# MCU.net
KiCad netlist of a schematic drawn in Altium Designer
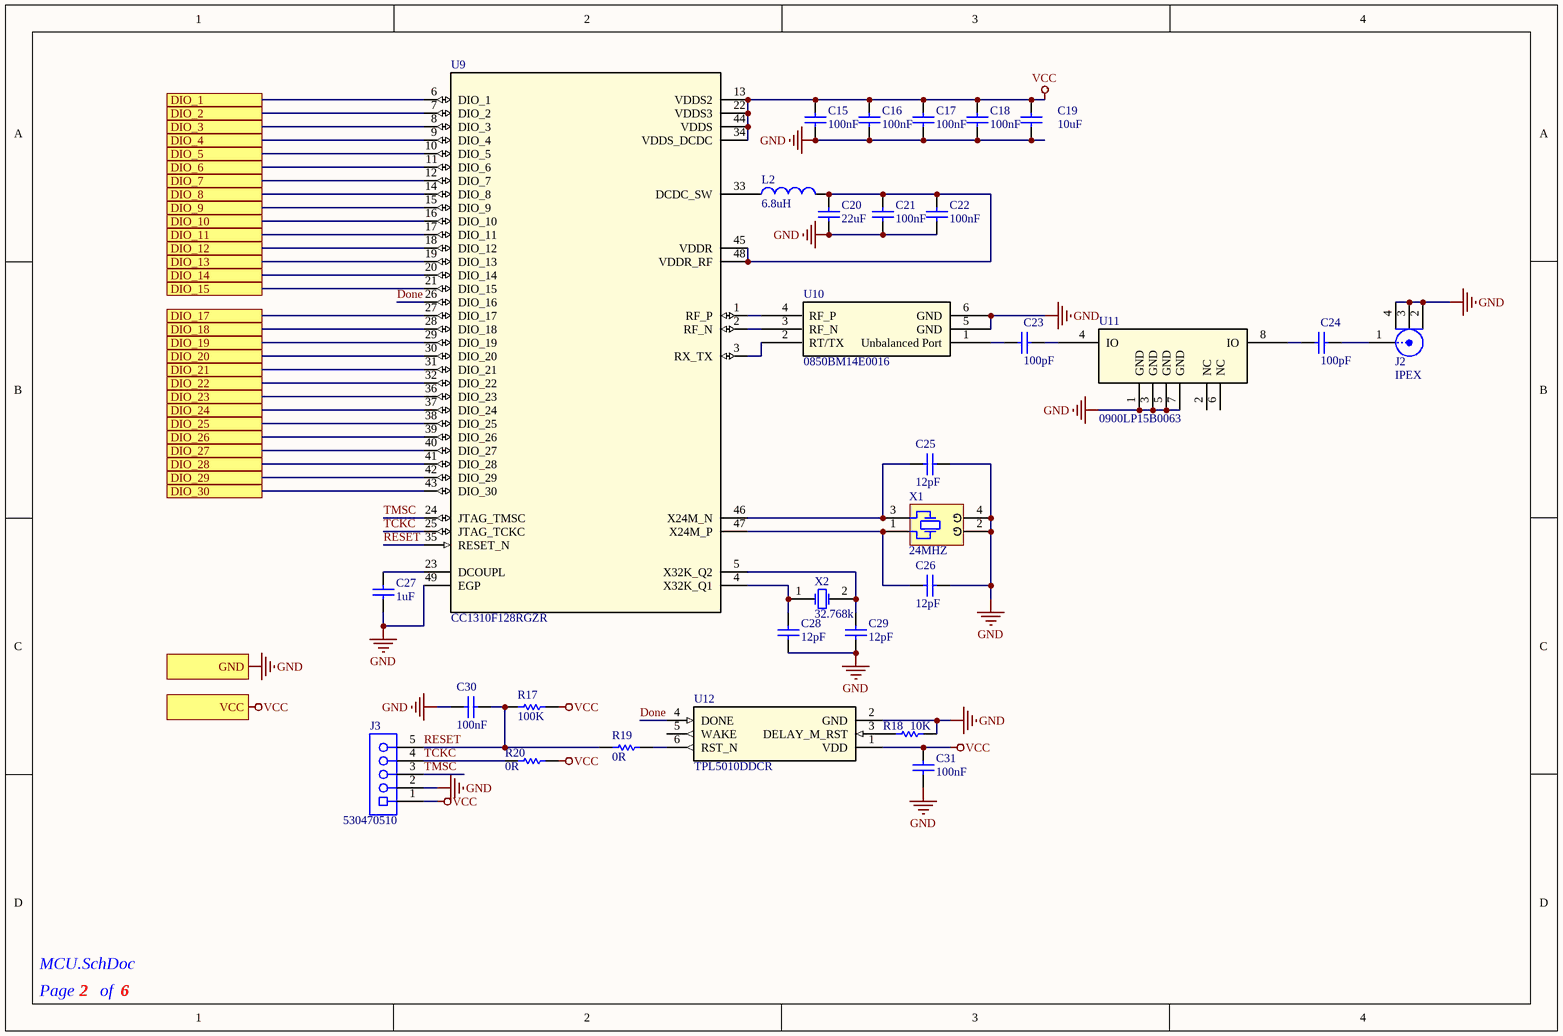
[diagram p0: MCU.SchDoc]

(export (version "E")
  (design (tool "Eeschema 10.0.6"))
  (components
    (comp (ref "C15")
      (value "100nF")
      (footprint "R0603_C")
      (description "精度 ±10% \r\n容值 100nF \r\n额定电压 50V \r\n温漂系数（介质材料) X7R")
      (libsource (lib "00Lib") (part "100nF/0603/50V"))
    )
    (comp (ref "C16")
      (value "100nF")
      (footprint "R0603_C")
      (description "精度 ±10% \r\n容值 100nF \r\n额定电压 50V \r\n温漂系数（介质材料) X7R")
      (libsource (lib "00Lib") (part "100nF/0603/50V"))
    )
    (comp (ref "C17")
      (value "100nF")
      (footprint "R0603_C")
      (description "精度 ±10% \r\n容值 100nF \r\n额定电压 50V \r\n温漂系数（介质材料) X7R")
      (libsource (lib "00Lib") (part "100nF/0603/50V"))
    )
    (comp (ref "C18")
      (value "100nF")
      (footprint "R0603_C")
      (description "精度 ±10% \r\n容值 100nF \r\n额定电压 50V \r\n温漂系数（介质材料) X7R")
      (libsource (lib "00Lib") (part "100nF/0603/50V"))
    )
    (comp (ref "C19")
      (value "10uF")
      (footprint "R0805_C")
      (description "精度 ±10% \r\n容值 10uF \r\n额定电压 16V \r\n温漂系数（介质材料) X7R")
      (libsource (lib "00Lib") (part "10uF/0805/16V"))
    )
    (comp (ref "C20")
      (value "22uF")
      (footprint "R0805_C")
      (description "精度 ±20% \r\n容值 22uF \r\n额定电压 16V \r\n温漂系数（介质材料) X5R")
      (libsource (lib "00Lib") (part "22uF/0805/16V"))
    )
    (comp (ref "C21")
      (value "100nF")
      (footprint "R0603_C")
      (description "精度 ±10% \r\n容值 100nF \r\n额定电压 50V \r\n温漂系数（介质材料) X7R")
      (libsource (lib "00Lib") (part "100nF/0603/50V"))
    )
    (comp (ref "C22")
      (value "100nF")
      (footprint "R0603_C")
      (description "精度 ±10% \r\n容值 100nF \r\n额定电压 50V \r\n温漂系数（介质材料) X7R")
      (libsource (lib "00Lib") (part "100nF/0603/50V"))
    )
    (comp (ref "C23")
      (value "100pF")
      (footprint "R0402_C")
      (description "精度 ±5% \r\n容值 100pF \r\n额定电压 50V \r\n温漂系数（介质材料) C0G")
      (libsource (lib "00Lib") (part "100pF/0402/50V"))
    )
    (comp (ref "C24")
      (value "100pF")
      (footprint "R0402_C")
      (description "精度 ±5% \r\n容值 100pF \r\n额定电压 50V \r\n温漂系数（介质材料) C0G")
      (libsource (lib "00Lib") (part "100pF/0402/50V"))
    )
    (comp (ref "C25")
      (value "12pF")
      (footprint "R0402_C")
      (description "精度 ±1% \r\n容值 12pF \r\n额定电压 50V \r\n温漂系数（介质材料) C0G")
      (libsource (lib "00Lib") (part "12pF/0402/50V"))
    )
    (comp (ref "C26")
      (value "12pF")
      (footprint "R0402_C")
      (description "精度 ±1% \r\n容值 12pF \r\n额定电压 50V \r\n温漂系数（介质材料) C0G")
      (libsource (lib "00Lib") (part "12pF/0402/50V"))
    )
    (comp (ref "C27")
      (value "1uF")
      (footprint "R0603_C")
      (description "精度 ±10% \r\n容值 1uF \r\n额定电压 50V \r\n温漂系数（介质材料) X7R")
      (libsource (lib "00Lib") (part "1uF/0603/50V"))
    )
    (comp (ref "C28")
      (value "12pF")
      (footprint "R0402_C")
      (description "精度 ±1% \r\n容值 12pF \r\n额定电压 50V \r\n温漂系数（介质材料) C0G")
      (libsource (lib "00Lib") (part "12pF/0402/50V"))
    )
    (comp (ref "C29")
      (value "12pF")
      (footprint "R0402_C")
      (description "精度 ±1% \r\n容值 12pF \r\n额定电压 50V \r\n温漂系数（介质材料) C0G")
      (libsource (lib "00Lib") (part "12pF/0402/50V"))
    )
    (comp (ref "C30")
      (value "100nF")
      (footprint "R0603_C")
      (description "精度 ±10% \r\n容值 100nF \r\n额定电压 50V \r\n温漂系数（介质材料) X7R")
      (libsource (lib "00Lib") (part "100nF/0603/50V"))
    )
    (comp (ref "C31")
      (value "100nF")
      (footprint "R0603_C")
      (description "精度 ±10% \r\n容值 100nF \r\n额定电压 50V \r\n温漂系数（介质材料) X7R")
      (libsource (lib "00Lib") (part "100nF/0603/50V"))
    )
    (comp (ref "J2")
      (value "IPEX")
      (footprint "molex-73412")
      (description "RF同轴连接器（天线座）")
      (libsource (lib "00Lib") (part "73412-0110"))
    )
    (comp (ref "J3")
      (value "530470510")
      (footprint "1.25mm_p5")
      (description "MX1.25 直插 镀锡 5P 针座")
      (libsource (lib "00Lib") (part "Molex-530470510"))
    )
    (comp (ref "L2")
      (value "6.8uH")
      (footprint "R0805_L")
      (description "精度 ±10% \r\n电感值 6.8uH \r\n直流电阻（内阻） 250mΩ \r\n额定电流 250mA")
      (libsource (lib "00Lib") (part "6.8uH/0805"))
    )
    (comp (ref "R17")
      (value "100K")
      (footprint "R0603_R")
      (description "精度 ±1% \r\n阻值 100kΩ \r\n温度系数 ±100ppm/℃ \r\n功率 0.1W")
      (libsource (lib "00Lib") (part "100K/0603"))
    )
    (comp (ref "R18")
      (value "10K")
      (footprint "R0603_R")
      (description "精度 ±1% \r\n温度系数 ±100ppm/℃ \r\n阻值 10kΩ \r\n功率 0.1W")
      (libsource (lib "00Lib") (part "10K/0603"))
    )
    (comp (ref "R19")
      (value "0R")
      (footprint "R0603_R")
      (description "精度 ±1% \r\n阻值 0Ω \r\n功率 0.1W")
      (libsource (lib "00Lib") (part "0R/0603"))
    )
    (comp (ref "R20")
      (value "0R")
      (footprint "R0603_R")
      (description "精度 ±1% \r\n阻值 0Ω \r\n功率 0.1W")
      (libsource (lib "00Lib") (part "0R/0603"))
    )
    (comp (ref "U9")
      (value "CC1310F128RGZR")
      (footprint "RGZ0048A")
      (description "RF-MCU")
      (libsource (lib "00Lib") (part "CC1310F128RGZR"))
    )
    (comp (ref "U10")
      (value "0850BM14E0016")
      (footprint "6P0603")
      (description "770 - 860 860 - 928MHz\r\n-40°C to +85°C\r\nPmax 2W")
      (libsource (lib "00Lib") (part "0850BM14E0016"))
    )
    (comp (ref "U11")
      (value "0900LP15B0063")
      (footprint "8P0805")
      (libsource (lib "00Lib") (part "0900LP15B0063"))
    )
    (comp (ref "U12")
      (value "TPL5010DDCR")
      (footprint "DBV0006A_N")
      (description "看门狗")
      (libsource (lib "00Lib") (part "TPL5010DDCR"))
    )
    (comp (ref "X1")
      (value "24MHZ")
      (footprint "SMD-3225")
      (description "等效串联电阻（ESR） 40Ω \r\n无源贴片晶振 \r\n主频 24MHz \r\n频率公差 ±10ppm \r\n负载电容值 9pF \r\n工作温度 -40℃~85℃")
      (libsource (lib "00Lib") (part "X1E000021012700"))
    )
    (comp (ref "X2")
      (value "32.768k")
      (footprint "FC-135")
      (libsource (lib "00Lib") (part "FC-135 32.768KHz ±20ppm 12.5pF"))
    )
  )
  (nets
    (net (code "1") (name "/DIO_1") (class "Default")
      (node (ref "U9") (pin "6") (pinfunction "DIO_1_6") (pintype "bidirectional"))
    )
    (net (code "2") (name "/DIO_2") (class "Default")
      (node (ref "U9") (pin "7") (pinfunction "DIO_2_7") (pintype "bidirectional"))
    )
    (net (code "3") (name "/DIO_3") (class "Default")
      (node (ref "U9") (pin "8") (pinfunction "DIO_3_8") (pintype "bidirectional"))
    )
    (net (code "4") (name "/DIO_4") (class "Default")
      (node (ref "U9") (pin "9") (pinfunction "DIO_4_9") (pintype "bidirectional"))
    )
    (net (code "5") (name "/DIO_5") (class "Default")
      (node (ref "U9") (pin "10") (pinfunction "DIO_5_10") (pintype "bidirectional"))
    )
    (net (code "6") (name "/DIO_6") (class "Default")
      (node (ref "U9") (pin "11") (pinfunction "DIO_6_11") (pintype "bidirectional"))
    )
    (net (code "7") (name "/DIO_7") (class "Default")
      (node (ref "U9") (pin "12") (pinfunction "DIO_7_12") (pintype "bidirectional"))
    )
    (net (code "8") (name "/DIO_8") (class "Default")
      (node (ref "U9") (pin "14") (pinfunction "DIO_8_14") (pintype "bidirectional"))
    )
    (net (code "9") (name "/DIO_9") (class "Default")
      (node (ref "U9") (pin "15") (pinfunction "DIO_9_15") (pintype "bidirectional"))
    )
    (net (code "10") (name "/DIO_10") (class "Default")
      (node (ref "U9") (pin "16") (pinfunction "DIO_10_16") (pintype "bidirectional"))
    )
    (net (code "11") (name "/DIO_11") (class "Default")
      (node (ref "U9") (pin "17") (pinfunction "DIO_11_17") (pintype "bidirectional"))
    )
    (net (code "12") (name "/DIO_12") (class "Default")
      (node (ref "U9") (pin "18") (pinfunction "DIO_12_18") (pintype "bidirectional"))
    )
    (net (code "13") (name "/DIO_13") (class "Default")
      (node (ref "U9") (pin "19") (pinfunction "DIO_13_19") (pintype "bidirectional"))
    )
    (net (code "14") (name "/DIO_14") (class "Default")
      (node (ref "U9") (pin "20") (pinfunction "DIO_14_20") (pintype "bidirectional"))
    )
    (net (code "15") (name "/DIO_15") (class "Default")
      (node (ref "U9") (pin "21") (pinfunction "DIO_15_21") (pintype "bidirectional"))
    )
    (net (code "16") (name "/DIO_17") (class "Default")
      (node (ref "U9") (pin "27") (pinfunction "DIO_17_27") (pintype "bidirectional"))
    )
    (net (code "17") (name "/DIO_18") (class "Default")
      (node (ref "U9") (pin "28") (pinfunction "DIO_18_28") (pintype "bidirectional"))
    )
    (net (code "18") (name "/DIO_19") (class "Default")
      (node (ref "U9") (pin "29") (pinfunction "DIO_19_29") (pintype "bidirectional"))
    )
    (net (code "19") (name "/DIO_20") (class "Default")
      (node (ref "U9") (pin "30") (pinfunction "DIO_20_30") (pintype "bidirectional"))
    )
    (net (code "20") (name "/DIO_21") (class "Default")
      (node (ref "U9") (pin "31") (pinfunction "DIO_21_31") (pintype "bidirectional"))
    )
    (net (code "21") (name "/DIO_22") (class "Default")
      (node (ref "U9") (pin "32") (pinfunction "DIO_22_32") (pintype "bidirectional"))
    )
    (net (code "22") (name "/DIO_23") (class "Default")
      (node (ref "U9") (pin "36") (pinfunction "DIO_23_36") (pintype "bidirectional"))
    )
    (net (code "23") (name "/DIO_24") (class "Default")
      (node (ref "U9") (pin "37") (pinfunction "DIO_24_37") (pintype "bidirectional"))
    )
    (net (code "24") (name "/DIO_25") (class "Default")
      (node (ref "U9") (pin "38") (pinfunction "DIO_25_38") (pintype "bidirectional"))
    )
    (net (code "25") (name "/DIO_26") (class "Default")
      (node (ref "U9") (pin "39") (pinfunction "DIO_26_39") (pintype "bidirectional"))
    )
    (net (code "26") (name "/DIO_27") (class "Default")
      (node (ref "U9") (pin "40") (pinfunction "DIO_27_40") (pintype "bidirectional"))
    )
    (net (code "27") (name "/DIO_28") (class "Default")
      (node (ref "U9") (pin "41") (pinfunction "DIO_28_41") (pintype "bidirectional"))
    )
    (net (code "28") (name "/DIO_29") (class "Default")
      (node (ref "U9") (pin "42") (pinfunction "DIO_29_42") (pintype "bidirectional"))
    )
    (net (code "29") (name "/DIO_30") (class "Default")
      (node (ref "U9") (pin "43") (pinfunction "DIO_30_43") (pintype "bidirectional"))
    )
    (net (code "30") (name "/Done") (class "Default")
      (node (ref "U12") (pin "4") (pinfunction "DONE_4") (pintype "input"))
      (node (ref "U9") (pin "26") (pinfunction "DIO_16_26") (pintype "bidirectional"))
    )
    (net (code "31") (name "/RESET") (class "Default")
      (node (ref "C30") (pin "1") (pinfunction "1_1") (pintype "passive"))
      (node (ref "J3") (pin "5") (pinfunction "5_5") (pintype "passive"))
      (node (ref "R17") (pin "1") (pinfunction "1_1") (pintype "passive"))
      (node (ref "R19") (pin "2") (pinfunction "2_2") (pintype "passive"))
      (node (ref "U9") (pin "35") (pinfunction "RESET_N_35") (pintype "input"))
    )
    (net (code "32") (name "/TCKC") (class "Default")
      (node (ref "J3") (pin "4") (pinfunction "4_4") (pintype "passive"))
      (node (ref "R20") (pin "2") (pinfunction "2_2") (pintype "passive"))
      (node (ref "U9") (pin "25") (pinfunction "JTAG_TCKC_25") (pintype "bidirectional"))
    )
    (net (code "33") (name "/TMSC") (class "Default")
      (node (ref "J3") (pin "3") (pinfunction "3_3") (pintype "passive"))
      (node (ref "U9") (pin "24") (pinfunction "JTAG_TMSC_24") (pintype "bidirectional"))
    )
    (net (code "34") (name "GND") (class "Default")
      (node (ref "C15") (pin "1") (pinfunction "1_1") (pintype "passive"))
      (node (ref "C16") (pin "1") (pinfunction "1_1") (pintype "passive"))
      (node (ref "C17") (pin "1") (pinfunction "1_1") (pintype "passive"))
      (node (ref "C18") (pin "1") (pinfunction "1_1") (pintype "passive"))
      (node (ref "C19") (pin "1") (pinfunction "1_1") (pintype "passive"))
      (node (ref "C20") (pin "1") (pinfunction "1_1") (pintype "passive"))
      (node (ref "C21") (pin "1") (pinfunction "1_1") (pintype "passive"))
      (node (ref "C22") (pin "1") (pinfunction "1_1") (pintype "passive"))
      (node (ref "C25") (pin "1") (pinfunction "1_1") (pintype "passive"))
      (node (ref "C26") (pin "1") (pinfunction "1_1") (pintype "passive"))
      (node (ref "C27") (pin "1") (pinfunction "1_1") (pintype "passive"))
      (node (ref "C28") (pin "1") (pinfunction "1_1") (pintype "passive"))
      (node (ref "C29") (pin "1") (pinfunction "1_1") (pintype "passive"))
      (node (ref "C30") (pin "2") (pinfunction "2_2") (pintype "passive"))
      (node (ref "C31") (pin "1") (pinfunction "1_1") (pintype "passive"))
      (node (ref "J2") (pin "2") (pinfunction "2_2") (pintype "passive"))
      (node (ref "J2") (pin "3") (pinfunction "3_3") (pintype "passive"))
      (node (ref "J2") (pin "4") (pinfunction "4_4") (pintype "passive"))
      (node (ref "J3") (pin "2") (pinfunction "2_2") (pintype "passive"))
      (node (ref "R18") (pin "1") (pinfunction "1_1") (pintype "passive"))
      (node (ref "U10") (pin "5") (pinfunction "GND_5") (pintype "passive"))
      (node (ref "U10") (pin "6") (pinfunction "GND_6") (pintype "passive"))
      (node (ref "U11") (pin "1") (pinfunction "GND_1") (pintype "passive"))
      (node (ref "U11") (pin "3") (pinfunction "GND_3") (pintype "passive"))
      (node (ref "U11") (pin "5") (pinfunction "GND_5") (pintype "passive"))
      (node (ref "U11") (pin "7") (pinfunction "GND_7") (pintype "passive"))
      (node (ref "U12") (pin "2") (pinfunction "GND_2") (pintype "power_in"))
      (node (ref "U9") (pin "49") (pinfunction "EGP_49") (pintype "power_in"))
      (node (ref "X1") (pin "2") (pinfunction "GND_2") (pintype "power_in"))
      (node (ref "X1") (pin "4") (pinfunction "GND_4") (pintype "power_in"))
    )
    (net (code "35") (name "Net-(C23-Pad2)") (class "Default")
      (node (ref "C23") (pin "2") (pinfunction "2_2") (pintype "passive"))
      (node (ref "U11") (pin "4") (pinfunction "IO_4") (pintype "passive"))
    )
    (net (code "36") (name "Net-(C24-Pad1)") (class "Default")
      (node (ref "C24") (pin "1") (pinfunction "1_1") (pintype "passive"))
      (node (ref "U11") (pin "8") (pinfunction "IO_8") (pintype "passive"))
    )
    (net (code "37") (name "Net-(C24-Pad2)") (class "Default")
      (node (ref "C24") (pin "2") (pinfunction "2_2") (pintype "passive"))
      (node (ref "J2") (pin "1") (pinfunction "1_1") (pintype "passive"))
    )
    (net (code "38") (name "Net-(U9-DCDC_SW)") (class "Default")
      (node (ref "L2") (pin "1") (pinfunction "1_1") (pintype "passive"))
      (node (ref "U9") (pin "33") (pinfunction "DCDC_SW_33") (pintype "power_in"))
    )
    (net (code "39") (name "Net-(U9-DCOUPL)") (class "Default")
      (node (ref "C27") (pin "2") (pinfunction "2_2") (pintype "passive"))
      (node (ref "U9") (pin "23") (pinfunction "DCOUPL_23") (pintype "passive"))
    )
    (net (code "40") (name "Net-(U9-VDDR)") (class "Default")
      (node (ref "C20") (pin "2") (pinfunction "2_2") (pintype "passive"))
      (node (ref "C21") (pin "2") (pinfunction "2_2") (pintype "passive"))
      (node (ref "C22") (pin "2") (pinfunction "2_2") (pintype "passive"))
      (node (ref "L2") (pin "2") (pinfunction "2_2") (pintype "passive"))
      (node (ref "U9") (pin "45") (pinfunction "VDDR_45") (pintype "power_in"))
      (node (ref "U9") (pin "48") (pinfunction "VDDR_RF_48") (pintype "power_in"))
    )
    (net (code "41") (name "Net-(U9-X24M_N)") (class "Default")
      (node (ref "C25") (pin "2") (pinfunction "2_2") (pintype "passive"))
      (node (ref "U9") (pin "46") (pinfunction "X24M_N_46") (pintype "passive"))
      (node (ref "X1") (pin "3") (pinfunction "3_3") (pintype "passive"))
    )
    (net (code "42") (name "Net-(U9-X24M_P)") (class "Default")
      (node (ref "C26") (pin "2") (pinfunction "2_2") (pintype "passive"))
      (node (ref "U9") (pin "47") (pinfunction "X24M_P_47") (pintype "passive"))
      (node (ref "X1") (pin "1") (pinfunction "1_1") (pintype "passive"))
    )
    (net (code "43") (name "Net-(U9-X32K_Q1)") (class "Default")
      (node (ref "C28") (pin "2") (pinfunction "2_2") (pintype "passive"))
      (node (ref "U9") (pin "4") (pinfunction "X32K_Q1_4") (pintype "passive"))
      (node (ref "X2") (pin "1") (pinfunction "OSC1_1") (pintype "passive"))
    )
    (net (code "44") (name "Net-(U9-X32K_Q2)") (class "Default")
      (node (ref "C29") (pin "2") (pinfunction "2_2") (pintype "passive"))
      (node (ref "U9") (pin "5") (pinfunction "X32K_Q2_5") (pintype "passive"))
      (node (ref "X2") (pin "2") (pinfunction "OSC2_2") (pintype "passive"))
    )
    (net (code "45") (name "Net-(U10-RF_N)") (class "Default")
      (node (ref "U10") (pin "3") (pinfunction "RF_N_3") (pintype "passive"))
      (node (ref "U9") (pin "2") (pinfunction "RF_N_2") (pintype "bidirectional"))
    )
    (net (code "46") (name "Net-(U10-RF_P)") (class "Default")
      (node (ref "U10") (pin "4") (pinfunction "RF_P_4") (pintype "passive"))
      (node (ref "U9") (pin "1") (pinfunction "RF_P_1") (pintype "bidirectional"))
    )
    (net (code "47") (name "Net-(U10-RT{slash}TX)") (class "Default")
      (node (ref "U10") (pin "2") (pinfunction "RT/TX_2") (pintype "passive"))
      (node (ref "U9") (pin "3") (pinfunction "RX_TX_3") (pintype "bidirectional"))
    )
    (net (code "48") (name "Net-(U10-Unbalanced_Port)") (class "Default")
      (node (ref "C23") (pin "1") (pinfunction "1_1") (pintype "passive"))
      (node (ref "U10") (pin "1") (pinfunction "Unbalanced_Port_1") (pintype "passive"))
    )
    (net (code "49") (name "Net-(U12-DELAY_M_RST)") (class "Default")
      (node (ref "R18") (pin "2") (pinfunction "2_2") (pintype "passive"))
      (node (ref "U12") (pin "3") (pinfunction "DELAY_M_RST_3") (pintype "input"))
    )
    (net (code "50") (name "Net-(U12-RST_N)") (class "Default")
      (node (ref "R19") (pin "1") (pinfunction "1_1") (pintype "passive"))
      (node (ref "U12") (pin "6") (pinfunction "RST_N_6") (pintype "output"))
    )
    (net (code "51") (name "VCC") (class "Default")
      (node (ref "C15") (pin "2") (pinfunction "2_2") (pintype "passive"))
      (node (ref "C16") (pin "2") (pinfunction "2_2") (pintype "passive"))
      (node (ref "C17") (pin "2") (pinfunction "2_2") (pintype "passive"))
      (node (ref "C18") (pin "2") (pinfunction "2_2") (pintype "passive"))
      (node (ref "C19") (pin "2") (pinfunction "2_2") (pintype "passive"))
      (node (ref "C31") (pin "2") (pinfunction "2_2") (pintype "passive"))
      (node (ref "J3") (pin "1") (pinfunction "1_1") (pintype "passive"))
      (node (ref "R17") (pin "2") (pinfunction "2_2") (pintype "passive"))
      (node (ref "R20") (pin "1") (pinfunction "1_1") (pintype "passive"))
      (node (ref "U12") (pin "1") (pinfunction "VDD_1") (pintype "power_in"))
      (node (ref "U9") (pin "13") (pinfunction "VDDS2_13") (pintype "power_in"))
      (node (ref "U9") (pin "22") (pinfunction "VDDS3_22") (pintype "power_in"))
      (node (ref "U9") (pin "34") (pinfunction "VDDS_DCDC_34") (pintype "power_in"))
      (node (ref "U9") (pin "44") (pinfunction "VDDS_44") (pintype "power_in"))
    )
    (net (code "52") (name "unconnected-(U11-NC-Pad2)") (class "Default")
      (node (ref "U11") (pin "2") (pinfunction "NC_2") (pintype "passive"))
    )
    (net (code "53") (name "unconnected-(U11-NC-Pad6)") (class "Default")
      (node (ref "U11") (pin "6") (pinfunction "NC_6") (pintype "passive"))
    )
    (net (code "54") (name "unconnected-(U12-WAKE-Pad5)") (class "Default")
      (node (ref "U12") (pin "5") (pinfunction "WAKE_5") (pintype "output"))
    )
  )
)
